# MOTOR_CONTROL.net
KiCad netlist of a schematic drawn in Altium Designer
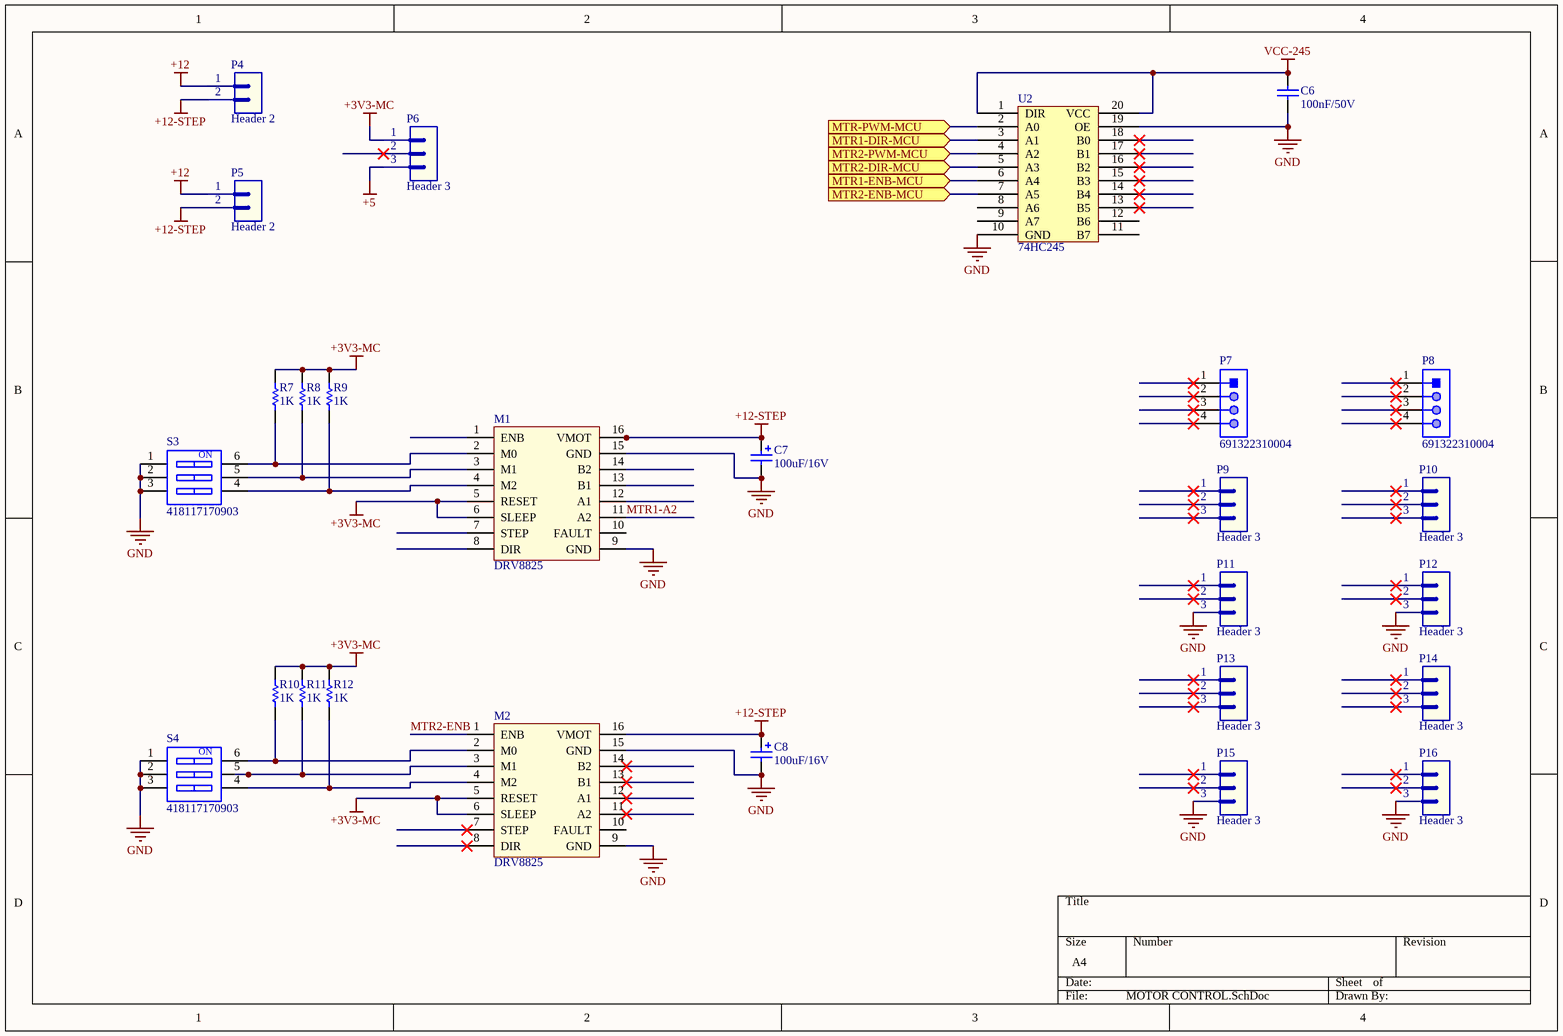
[diagram p0: MOTOR CONTROL.SchDoc]

(export (version "E")
  (design (tool "Eeschema 10.0.6"))
  (components
    (comp (ref "C6")
      (value "100nF/50V")
      (footprint "CAP-SM-0805")
      (description "CAP CER 0.1UF 50V Y5V 0805")
      (fields
        (field (name "MANUFACTURER") "Samsung Electro-Mechanics")
        (field (name "MANUFACTURER PART NUMBER") "CL21F104ZBCNNNC")
      )
      (libsource (lib "Capacitor") (part "Cap-100nF-50V-0805"))
    )
    (comp (ref "C7")
      (value "100uF/16V")
      (footprint "CAP-SM-AL-SIZE-D-D6L6")
      (description "CAP ALUM 100UF 20% 16V SMD")
      (fields
        (field (name "MANUFACTURER") "Nichicon")
        (field (name "MANUFACTURER PART NUMBER") "UWX1C101MCL1GB")
      )
      (libsource (lib "Capacitor") (part "Cap-Al-100uF-16V-D6L5"))
    )
    (comp (ref "C8")
      (value "100uF/16V")
      (footprint "CAP-SM-AL-SIZE-D-D6L6")
      (description "CAP ALUM 100UF 20% 16V SMD")
      (fields
        (field (name "MANUFACTURER") "Nichicon")
        (field (name "MANUFACTURER PART NUMBER") "UWX1C101MCL1GB")
      )
      (libsource (lib "Capacitor") (part "Cap-Al-100uF-16V-D6L5"))
    )
    (comp (ref "M1") (value "DRV8825") (libsource (lib "MyLibrary1") (part "DRV8825")))
    (comp (ref "M2") (value "DRV8825") (libsource (lib "MyLibrary1") (part "DRV8825")))
    (comp (ref "P4")
      (value "Header 2")
      (footprint "JP2")
      (description "Header, 2-Pin")
      (fields (field (name "PUBLISHER") "Altium Limited"))
      (libsource (lib "PIF_C16_lib") (part "Header 2"))
    )
    (comp (ref "P5")
      (value "Header 2")
      (footprint "JP2")
      (description "Header, 2-Pin")
      (fields (field (name "PUBLISHER") "Altium Limited"))
      (libsource (lib "PIF_C16_lib") (part "Header 2"))
    )
    (comp (ref "P6")
      (value "Header 3")
      (footprint "JP3")
      (description "Header, 3-Pin")
      (fields (field (name "PUBLISHER") "Altium Limited"))
      (libsource (lib "PIF_C16_lib") (part "Header 3"))
    )
    (comp (ref "P7")
      (value "691322310004")
      (footprint "691322310004")
      (description "WR-TBL Serie 322 Horizontal PCB Header, Pluggable, pitch 3.81mm, 4p")
      (fields (field (name "PUBLISHER") "Wurth Elektronik"))
      (libsource (lib "691111710003_Altium_WR-TBL_rev19a") (part "691322310004"))
    )
    (comp (ref "P8")
      (value "691322310004")
      (footprint "691322310004")
      (description "WR-TBL Serie 322 Horizontal PCB Header, Pluggable, pitch 3.81mm, 4p")
      (fields (field (name "PUBLISHER") "Wurth Elektronik"))
      (libsource (lib "691111710003_Altium_WR-TBL_rev19a") (part "691322310004"))
    )
    (comp (ref "P9")
      (value "Header 3")
      (footprint "JP3")
      (description "Header, 3-Pin")
      (fields (field (name "PUBLISHER") "Altium Limited"))
      (libsource (lib "PIF_C16_lib") (part "Header 3"))
    )
    (comp (ref "P10")
      (value "Header 3")
      (footprint "JP3")
      (description "Header, 3-Pin")
      (fields (field (name "PUBLISHER") "Altium Limited"))
      (libsource (lib "PIF_C16_lib") (part "Header 3"))
    )
    (comp (ref "P11")
      (value "Header 3")
      (footprint "JP3")
      (description "Header, 3-Pin")
      (fields (field (name "PUBLISHER") "Altium Limited"))
      (libsource (lib "PIF_C16_lib") (part "Header 3"))
    )
    (comp (ref "P12")
      (value "Header 3")
      (footprint "JP3")
      (description "Header, 3-Pin")
      (fields (field (name "PUBLISHER") "Altium Limited"))
      (libsource (lib "PIF_C16_lib") (part "Header 3"))
    )
    (comp (ref "P13")
      (value "Header 3")
      (footprint "JP3")
      (description "Header, 3-Pin")
      (fields (field (name "PUBLISHER") "Altium Limited"))
      (libsource (lib "PIF_C16_lib") (part "Header 3"))
    )
    (comp (ref "P14")
      (value "Header 3")
      (footprint "JP3")
      (description "Header, 3-Pin")
      (fields (field (name "PUBLISHER") "Altium Limited"))
      (libsource (lib "PIF_C16_lib") (part "Header 3"))
    )
    (comp (ref "P15")
      (value "Header 3")
      (footprint "JP3")
      (description "Header, 3-Pin")
      (fields (field (name "PUBLISHER") "Altium Limited"))
      (libsource (lib "PIF_C16_lib") (part "Header 3"))
    )
    (comp (ref "P16")
      (value "Header 3")
      (footprint "JP3")
      (description "Header, 3-Pin")
      (fields (field (name "PUBLISHER") "Altium Limited"))
      (libsource (lib "PIF_C16_lib") (part "Header 3"))
    )
    (comp (ref "R7")
      (value "1K")
      (footprint "Resistor:RES-SM-0805")
      (description "RES 1K OHM 1% 1/4W 0805")
      (fields
        (field (name "MANUFACTURER") "Stackpole Electronics Inc")
        (field (name "MANUFACTURER PART NUMBER") "RNCP0805FTD1K00")
      )
      (libsource (lib "Resistor") (part "Res-1K-0805"))
    )
    (comp (ref "R8")
      (value "1K")
      (footprint "Resistor:RES-SM-0805")
      (description "RES 1K OHM 1% 1/4W 0805")
      (fields
        (field (name "MANUFACTURER") "Stackpole Electronics Inc")
        (field (name "MANUFACTURER PART NUMBER") "RNCP0805FTD1K00")
      )
      (libsource (lib "Resistor") (part "Res-1K-0805"))
    )
    (comp (ref "R9")
      (value "1K")
      (footprint "Resistor:RES-SM-0805")
      (description "RES 1K OHM 1% 1/4W 0805")
      (fields
        (field (name "MANUFACTURER") "Stackpole Electronics Inc")
        (field (name "MANUFACTURER PART NUMBER") "RNCP0805FTD1K00")
      )
      (libsource (lib "Resistor") (part "Res-1K-0805"))
    )
    (comp (ref "R10")
      (value "1K")
      (footprint "Resistor:RES-SM-0805")
      (description "RES 1K OHM 1% 1/4W 0805")
      (fields
        (field (name "MANUFACTURER") "Stackpole Electronics Inc")
        (field (name "MANUFACTURER PART NUMBER") "RNCP0805FTD1K00")
      )
      (libsource (lib "Resistor") (part "Res-1K-0805"))
    )
    (comp (ref "R11")
      (value "1K")
      (footprint "Resistor:RES-SM-0805")
      (description "RES 1K OHM 1% 1/4W 0805")
      (fields
        (field (name "MANUFACTURER") "Stackpole Electronics Inc")
        (field (name "MANUFACTURER PART NUMBER") "RNCP0805FTD1K00")
      )
      (libsource (lib "Resistor") (part "Res-1K-0805"))
    )
    (comp (ref "R12")
      (value "1K")
      (footprint "Resistor:RES-SM-0805")
      (description "RES 1K OHM 1% 1/4W 0805")
      (fields
        (field (name "MANUFACTURER") "Stackpole Electronics Inc")
        (field (name "MANUFACTURER PART NUMBER") "RNCP0805FTD1K00")
      )
      (libsource (lib "Resistor") (part "Res-1K-0805"))
    )
    (comp (ref "S3")
      (value "418117170903")
      (footprint "418117170903")
      (description "WS-DITV Compact THT Dip Switch, Flat Actuator, pitch 2.54mm, 3p")
      (fields (field (name "PUBLISHER") "Wurth Elektronik"))
      (libsource (lib "418117170903_Altium_WS-DITV_rev19a") (part "418117170903"))
    )
    (comp (ref "S4")
      (value "418117170903")
      (footprint "418117170903")
      (description "WS-DITV Compact THT Dip Switch, Flat Actuator, pitch 2.54mm, 3p")
      (fields (field (name "PUBLISHER") "Wurth Elektronik"))
      (libsource (lib "418117170903_Altium_WS-DITV_rev19a") (part "418117170903"))
    )
    (comp (ref "U2")
      (value "74HC245")
      (footprint "DIP20/W0.3")
      (description "Octal bus tranceiver")
      (libsource (lib "Library1") (part "74HC245"))
    )
  )
  (nets
    (net (code "1") (name "+3V3-MC") (class "Default")
      (node (ref "M1") (pin "5") (pinfunction "RESET_5") (pintype "passive"))
      (node (ref "M1") (pin "6") (pinfunction "SLEEP_6") (pintype "passive"))
      (node (ref "M2") (pin "5") (pinfunction "RESET_5") (pintype "passive"))
      (node (ref "M2") (pin "6") (pinfunction "SLEEP_6") (pintype "passive"))
      (node (ref "P6") (pin "1") (pinfunction "1_1") (pintype "passive"))
      (node (ref "R10") (pin "2") (pinfunction "2_2") (pintype "passive"))
      (node (ref "R11") (pin "2") (pinfunction "2_2") (pintype "passive"))
      (node (ref "R12") (pin "2") (pinfunction "2_2") (pintype "passive"))
      (node (ref "R7") (pin "2") (pinfunction "2_2") (pintype "passive"))
      (node (ref "R8") (pin "2") (pinfunction "2_2") (pintype "passive"))
      (node (ref "R9") (pin "2") (pinfunction "2_2") (pintype "passive"))
    )
    (net (code "2") (name "+5") (class "Default")
      (node (ref "P6") (pin "3") (pinfunction "3_3") (pintype "passive"))
    )
    (net (code "3") (name "+12") (class "Default")
      (node (ref "P4") (pin "1") (pinfunction "1_1") (pintype "passive"))
      (node (ref "P5") (pin "1") (pinfunction "1_1") (pintype "passive"))
    )
    (net (code "4") (name "+12-STEP") (class "Default")
      (node (ref "C7") (pin "1") (pinfunction "1_1") (pintype "passive"))
      (node (ref "C8") (pin "1") (pinfunction "1_1") (pintype "passive"))
      (node (ref "M1") (pin "16") (pinfunction "VMOT_16") (pintype "passive"))
      (node (ref "M2") (pin "16") (pinfunction "VMOT_16") (pintype "passive"))
      (node (ref "P4") (pin "2") (pinfunction "2_2") (pintype "passive"))
      (node (ref "P5") (pin "2") (pinfunction "2_2") (pintype "passive"))
    )
    (net (code "5") (name "/MTR-PWM-MCU") (class "Default")
      (node (ref "U2") (pin "2") (pinfunction "A0_2") (pintype "passive"))
    )
    (net (code "6") (name "/MTR1-A2") (class "Default")
      (node (ref "M1") (pin "11") (pinfunction "A2_11") (pintype "passive"))
    )
    (net (code "7") (name "/MTR1-DIR-MCU") (class "Default")
      (node (ref "U2") (pin "3") (pinfunction "A1_3") (pintype "passive"))
    )
    (net (code "8") (name "/MTR1-ENB-MCU") (class "Default")
      (node (ref "U2") (pin "6") (pinfunction "A4_6") (pintype "passive"))
    )
    (net (code "9") (name "/MTR2-DIR-MCU") (class "Default")
      (node (ref "U2") (pin "5") (pinfunction "A3_5") (pintype "passive"))
    )
    (net (code "10") (name "/MTR2-ENB") (class "Default")
      (node (ref "M2") (pin "1") (pinfunction "ENB_1") (pintype "passive"))
    )
    (net (code "11") (name "/MTR2-ENB-MCU") (class "Default")
      (node (ref "U2") (pin "7") (pinfunction "A5_7") (pintype "passive"))
    )
    (net (code "12") (name "/MTR2-PWM-MCU") (class "Default")
      (node (ref "U2") (pin "4") (pinfunction "A2_4") (pintype "passive"))
    )
    (net (code "13") (name "GND") (class "Default")
      (node (ref "C6") (pin "1") (pinfunction "1_1") (pintype "passive"))
      (node (ref "C7") (pin "2") (pinfunction "2_2") (pintype "passive"))
      (node (ref "C8") (pin "2") (pinfunction "2_2") (pintype "passive"))
      (node (ref "M1") (pin "15") (pinfunction "GND_15") (pintype "passive"))
      (node (ref "M1") (pin "9") (pinfunction "GND_9") (pintype "passive"))
      (node (ref "M2") (pin "15") (pinfunction "GND_15") (pintype "passive"))
      (node (ref "M2") (pin "9") (pinfunction "GND_9") (pintype "passive"))
      (node (ref "P11") (pin "3") (pinfunction "3_3") (pintype "passive"))
      (node (ref "P12") (pin "3") (pinfunction "3_3") (pintype "passive"))
      (node (ref "P15") (pin "3") (pinfunction "3_3") (pintype "passive"))
      (node (ref "P16") (pin "3") (pinfunction "3_3") (pintype "passive"))
      (node (ref "S3") (pin "1") (pinfunction "1_1") (pintype "passive"))
      (node (ref "S3") (pin "2") (pinfunction "2_2") (pintype "passive"))
      (node (ref "S3") (pin "3") (pinfunction "3_3") (pintype "passive"))
      (node (ref "S4") (pin "1") (pinfunction "1_1") (pintype "passive"))
      (node (ref "S4") (pin "2") (pinfunction "2_2") (pintype "passive"))
      (node (ref "S4") (pin "3") (pinfunction "3_3") (pintype "passive"))
      (node (ref "U2") (pin "10") (pinfunction "GND_10") (pintype "power_in"))
      (node (ref "U2") (pin "19") (pinfunction "OE_19") (pintype "passive"))
    )
    (net (code "14") (name "Net-(M1-M0)") (class "Default")
      (node (ref "M1") (pin "2") (pinfunction "M0_2") (pintype "passive"))
      (node (ref "R7") (pin "1") (pinfunction "1_1") (pintype "passive"))
      (node (ref "S3") (pin "6") (pinfunction "6_6") (pintype "passive"))
    )
    (net (code "15") (name "Net-(M1-M1)") (class "Default")
      (node (ref "M1") (pin "3") (pinfunction "M1_3") (pintype "passive"))
      (node (ref "R8") (pin "1") (pinfunction "1_1") (pintype "passive"))
      (node (ref "S3") (pin "5") (pinfunction "5_5") (pintype "passive"))
    )
    (net (code "16") (name "Net-(M1-M2)") (class "Default")
      (node (ref "M1") (pin "4") (pinfunction "M2_4") (pintype "passive"))
      (node (ref "R9") (pin "1") (pinfunction "1_1") (pintype "passive"))
      (node (ref "S3") (pin "4") (pinfunction "4_4") (pintype "passive"))
    )
    (net (code "17") (name "Net-(M2-M0)") (class "Default")
      (node (ref "M2") (pin "2") (pinfunction "M0_2") (pintype "passive"))
      (node (ref "R10") (pin "1") (pinfunction "1_1") (pintype "passive"))
      (node (ref "S4") (pin "6") (pinfunction "6_6") (pintype "passive"))
    )
    (net (code "18") (name "Net-(M2-M1)") (class "Default")
      (node (ref "M2") (pin "3") (pinfunction "M1_3") (pintype "passive"))
      (node (ref "R11") (pin "1") (pinfunction "1_1") (pintype "passive"))
      (node (ref "S4") (pin "5") (pinfunction "5_5") (pintype "passive"))
    )
    (net (code "19") (name "Net-(M2-M2)") (class "Default")
      (node (ref "M2") (pin "4") (pinfunction "M2_4") (pintype "passive"))
      (node (ref "R12") (pin "1") (pinfunction "1_1") (pintype "passive"))
      (node (ref "S4") (pin "4") (pinfunction "4_4") (pintype "passive"))
    )
    (net (code "20") (name "VCC-245") (class "Default")
      (node (ref "C6") (pin "2") (pinfunction "2_2") (pintype "passive"))
      (node (ref "U2") (pin "1") (pinfunction "DIR_1") (pintype "passive"))
      (node (ref "U2") (pin "20") (pinfunction "VCC_20") (pintype "power_in"))
    )
    (net (code "21") (name "unconnected-(M1-A1-Pad12)") (class "Default")
      (node (ref "M1") (pin "12") (pinfunction "A1_12") (pintype "passive"))
    )
    (net (code "22") (name "unconnected-(M1-B1-Pad13)") (class "Default")
      (node (ref "M1") (pin "13") (pinfunction "B1_13") (pintype "passive"))
    )
    (net (code "23") (name "unconnected-(M1-B2-Pad14)") (class "Default")
      (node (ref "M1") (pin "14") (pinfunction "B2_14") (pintype "passive"))
    )
    (net (code "24") (name "unconnected-(M1-DIR-Pad8)") (class "Default")
      (node (ref "M1") (pin "8") (pinfunction "DIR_8") (pintype "passive"))
    )
    (net (code "25") (name "unconnected-(M1-ENB-Pad1)") (class "Default")
      (node (ref "M1") (pin "1") (pinfunction "ENB_1") (pintype "passive"))
    )
    (net (code "26") (name "unconnected-(M1-FAULT-Pad10)") (class "Default")
      (node (ref "M1") (pin "10") (pinfunction "FAULT_10") (pintype "passive"))
    )
    (net (code "27") (name "unconnected-(M1-STEP-Pad7)") (class "Default")
      (node (ref "M1") (pin "7") (pinfunction "STEP_7") (pintype "passive"))
    )
    (net (code "28") (name "unconnected-(M2-A1-Pad12)") (class "Default")
      (node (ref "M2") (pin "12") (pinfunction "A1_12") (pintype "passive+no_connect"))
    )
    (net (code "29") (name "unconnected-(M2-A2-Pad11)") (class "Default")
      (node (ref "M2") (pin "11") (pinfunction "A2_11") (pintype "passive+no_connect"))
    )
    (net (code "30") (name "unconnected-(M2-B1-Pad13)") (class "Default")
      (node (ref "M2") (pin "13") (pinfunction "B1_13") (pintype "passive+no_connect"))
    )
    (net (code "31") (name "unconnected-(M2-B2-Pad14)") (class "Default")
      (node (ref "M2") (pin "14") (pinfunction "B2_14") (pintype "passive+no_connect"))
    )
    (net (code "32") (name "unconnected-(M2-DIR-Pad8)") (class "Default")
      (node (ref "M2") (pin "8") (pinfunction "DIR_8") (pintype "passive+no_connect"))
    )
    (net (code "33") (name "unconnected-(M2-FAULT-Pad10)") (class "Default")
      (node (ref "M2") (pin "10") (pinfunction "FAULT_10") (pintype "passive"))
    )
    (net (code "34") (name "unconnected-(M2-STEP-Pad7)") (class "Default")
      (node (ref "M2") (pin "7") (pinfunction "STEP_7") (pintype "passive+no_connect"))
    )
    (net (code "35") (name "unconnected-(P6-Pad2)") (class "Default")
      (node (ref "P6") (pin "2") (pinfunction "2_2") (pintype "passive+no_connect"))
    )
    (net (code "36") (name "unconnected-(P7-Pad1)") (class "Default")
      (node (ref "P7") (pin "1") (pinfunction "1_1") (pintype "passive+no_connect"))
    )
    (net (code "37") (name "unconnected-(P7-Pad2)") (class "Default")
      (node (ref "P7") (pin "2") (pinfunction "2_2") (pintype "passive+no_connect"))
    )
    (net (code "38") (name "unconnected-(P7-Pad3)") (class "Default")
      (node (ref "P7") (pin "3") (pinfunction "3_3") (pintype "passive+no_connect"))
    )
    (net (code "39") (name "unconnected-(P7-Pad4)") (class "Default")
      (node (ref "P7") (pin "4") (pinfunction "4_4") (pintype "passive+no_connect"))
    )
    (net (code "40") (name "unconnected-(P8-Pad1)") (class "Default")
      (node (ref "P8") (pin "1") (pinfunction "1_1") (pintype "passive+no_connect"))
    )
    (net (code "41") (name "unconnected-(P8-Pad2)") (class "Default")
      (node (ref "P8") (pin "2") (pinfunction "2_2") (pintype "passive+no_connect"))
    )
    (net (code "42") (name "unconnected-(P8-Pad3)") (class "Default")
      (node (ref "P8") (pin "3") (pinfunction "3_3") (pintype "passive+no_connect"))
    )
    (net (code "43") (name "unconnected-(P8-Pad4)") (class "Default")
      (node (ref "P8") (pin "4") (pinfunction "4_4") (pintype "passive+no_connect"))
    )
    (net (code "44") (name "unconnected-(P9-Pad1)") (class "Default")
      (node (ref "P9") (pin "1") (pinfunction "1_1") (pintype "passive+no_connect"))
    )
    (net (code "45") (name "unconnected-(P9-Pad2)") (class "Default")
      (node (ref "P9") (pin "2") (pinfunction "2_2") (pintype "passive+no_connect"))
    )
    (net (code "46") (name "unconnected-(P9-Pad3)") (class "Default")
      (node (ref "P9") (pin "3") (pinfunction "3_3") (pintype "passive+no_connect"))
    )
    (net (code "47") (name "unconnected-(P10-Pad1)") (class "Default")
      (node (ref "P10") (pin "1") (pinfunction "1_1") (pintype "passive+no_connect"))
    )
    (net (code "48") (name "unconnected-(P10-Pad2)") (class "Default")
      (node (ref "P10") (pin "2") (pinfunction "2_2") (pintype "passive+no_connect"))
    )
    (net (code "49") (name "unconnected-(P10-Pad3)") (class "Default")
      (node (ref "P10") (pin "3") (pinfunction "3_3") (pintype "passive+no_connect"))
    )
    (net (code "50") (name "unconnected-(P11-Pad1)") (class "Default")
      (node (ref "P11") (pin "1") (pinfunction "1_1") (pintype "passive+no_connect"))
    )
    (net (code "51") (name "unconnected-(P11-Pad2)") (class "Default")
      (node (ref "P11") (pin "2") (pinfunction "2_2") (pintype "passive+no_connect"))
    )
    (net (code "52") (name "unconnected-(P12-Pad1)") (class "Default")
      (node (ref "P12") (pin "1") (pinfunction "1_1") (pintype "passive+no_connect"))
    )
    (net (code "53") (name "unconnected-(P12-Pad2)") (class "Default")
      (node (ref "P12") (pin "2") (pinfunction "2_2") (pintype "passive+no_connect"))
    )
    (net (code "54") (name "unconnected-(P13-Pad1)") (class "Default")
      (node (ref "P13") (pin "1") (pinfunction "1_1") (pintype "passive+no_connect"))
    )
    (net (code "55") (name "unconnected-(P13-Pad2)") (class "Default")
      (node (ref "P13") (pin "2") (pinfunction "2_2") (pintype "passive+no_connect"))
    )
    (net (code "56") (name "unconnected-(P13-Pad3)") (class "Default")
      (node (ref "P13") (pin "3") (pinfunction "3_3") (pintype "passive+no_connect"))
    )
    (net (code "57") (name "unconnected-(P14-Pad1)") (class "Default")
      (node (ref "P14") (pin "1") (pinfunction "1_1") (pintype "passive+no_connect"))
    )
    (net (code "58") (name "unconnected-(P14-Pad2)") (class "Default")
      (node (ref "P14") (pin "2") (pinfunction "2_2") (pintype "passive+no_connect"))
    )
    (net (code "59") (name "unconnected-(P14-Pad3)") (class "Default")
      (node (ref "P14") (pin "3") (pinfunction "3_3") (pintype "passive+no_connect"))
    )
    (net (code "60") (name "unconnected-(P15-Pad1)") (class "Default")
      (node (ref "P15") (pin "1") (pinfunction "1_1") (pintype "passive+no_connect"))
    )
    (net (code "61") (name "unconnected-(P15-Pad2)") (class "Default")
      (node (ref "P15") (pin "2") (pinfunction "2_2") (pintype "passive+no_connect"))
    )
    (net (code "62") (name "unconnected-(P16-Pad1)") (class "Default")
      (node (ref "P16") (pin "1") (pinfunction "1_1") (pintype "passive+no_connect"))
    )
    (net (code "63") (name "unconnected-(P16-Pad2)") (class "Default")
      (node (ref "P16") (pin "2") (pinfunction "2_2") (pintype "passive+no_connect"))
    )
    (net (code "64") (name "unconnected-(U2-A6-Pad8)") (class "Default")
      (node (ref "U2") (pin "8") (pinfunction "A6_8") (pintype "passive"))
    )
    (net (code "65") (name "unconnected-(U2-A7-Pad9)") (class "Default")
      (node (ref "U2") (pin "9") (pinfunction "A7_9") (pintype "passive"))
    )
    (net (code "66") (name "unconnected-(U2-B0-Pad18)") (class "Default")
      (node (ref "U2") (pin "18") (pinfunction "B0_18") (pintype "passive+no_connect"))
    )
    (net (code "67") (name "unconnected-(U2-B1-Pad17)") (class "Default")
      (node (ref "U2") (pin "17") (pinfunction "B1_17") (pintype "passive+no_connect"))
    )
    (net (code "68") (name "unconnected-(U2-B2-Pad16)") (class "Default")
      (node (ref "U2") (pin "16") (pinfunction "B2_16") (pintype "passive+no_connect"))
    )
    (net (code "69") (name "unconnected-(U2-B3-Pad15)") (class "Default")
      (node (ref "U2") (pin "15") (pinfunction "B3_15") (pintype "passive+no_connect"))
    )
    (net (code "70") (name "unconnected-(U2-B4-Pad14)") (class "Default")
      (node (ref "U2") (pin "14") (pinfunction "B4_14") (pintype "passive+no_connect"))
    )
    (net (code "71") (name "unconnected-(U2-B5-Pad13)") (class "Default")
      (node (ref "U2") (pin "13") (pinfunction "B5_13") (pintype "passive+no_connect"))
    )
    (net (code "72") (name "unconnected-(U2-B6-Pad12)") (class "Default")
      (node (ref "U2") (pin "12") (pinfunction "B6_12") (pintype "passive"))
    )
    (net (code "73") (name "unconnected-(U2-B7-Pad11)") (class "Default")
      (node (ref "U2") (pin "11") (pinfunction "B7_11") (pintype "passive"))
    )
  )
)
